# control_board_MCU.net
KiCad netlist of a schematic drawn in EAGLE
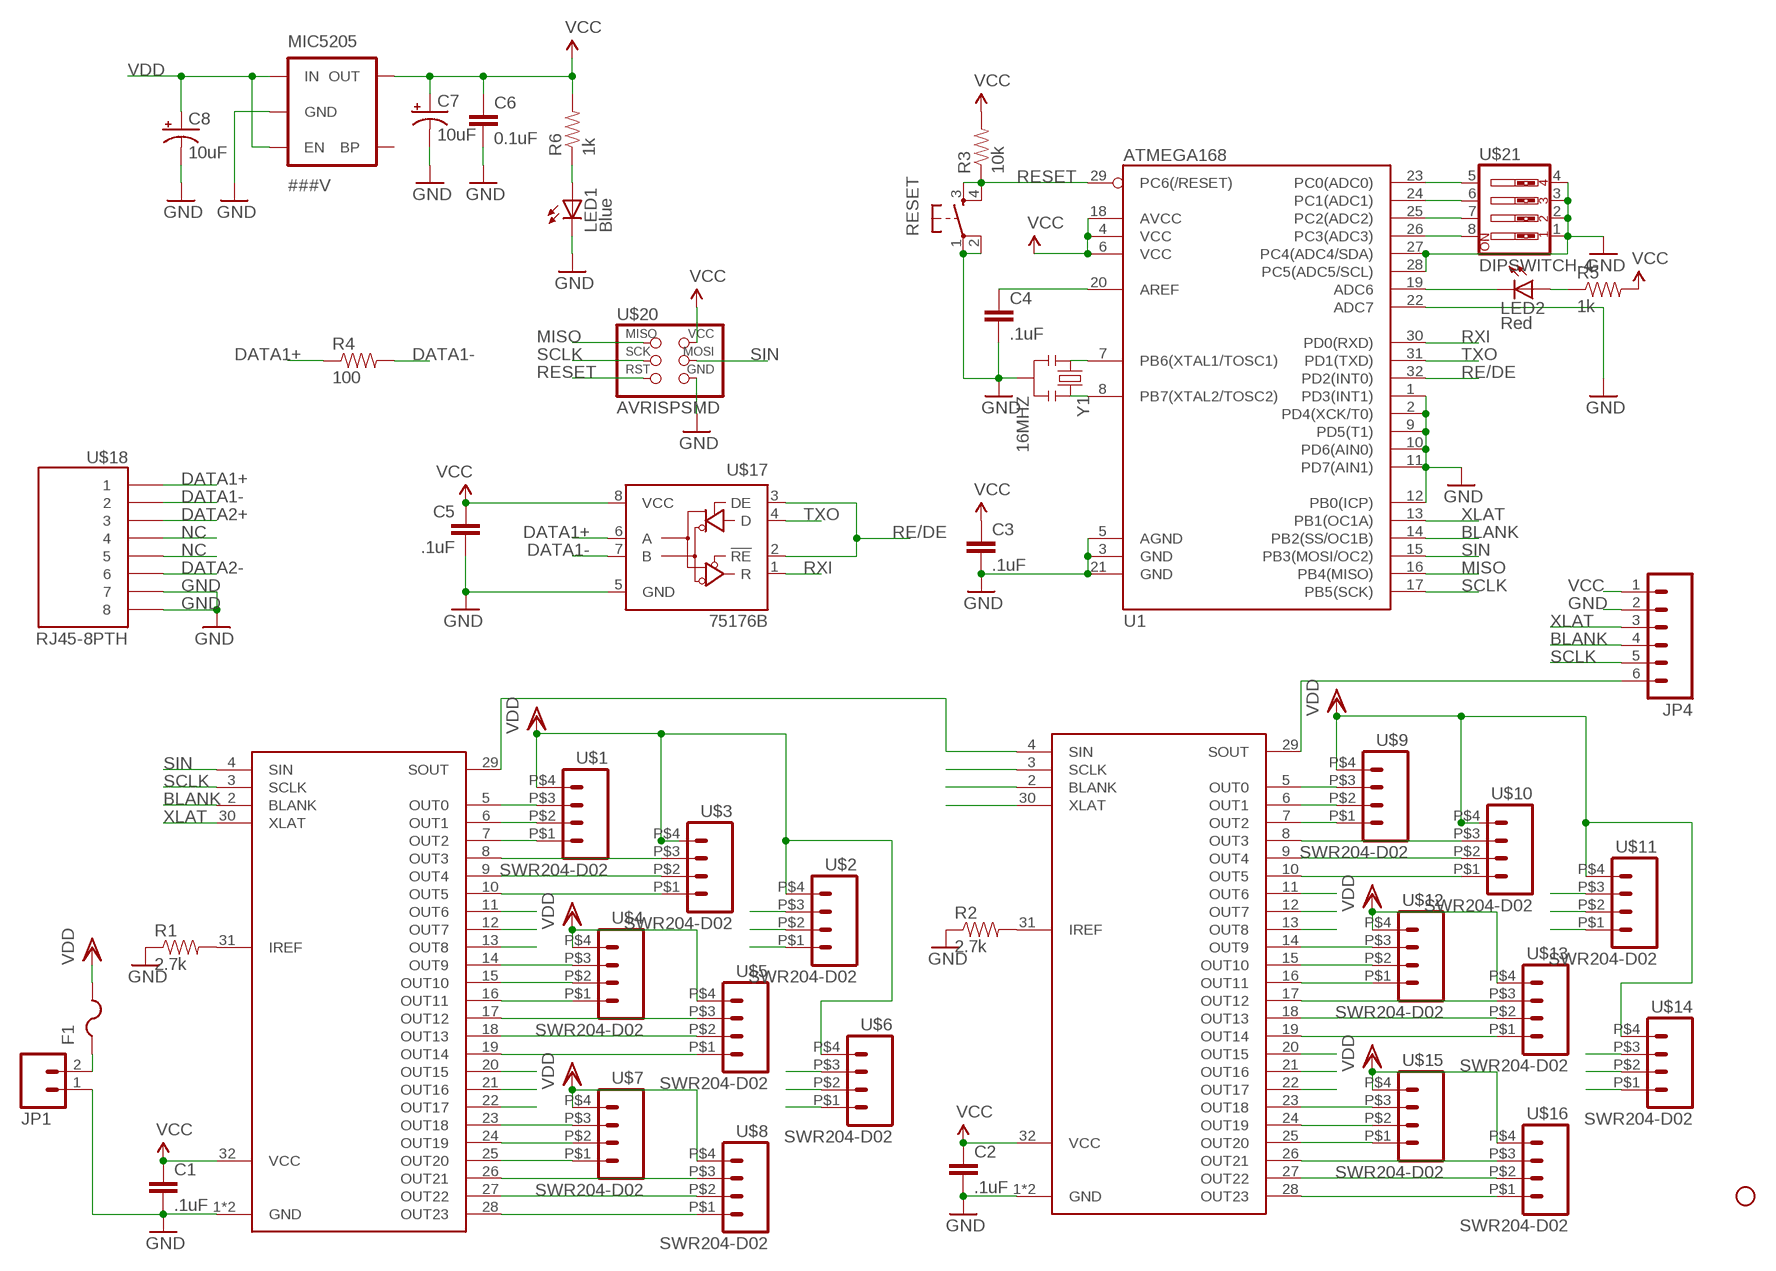
[diagram p0: schematic, sheet 1]

(export (version "E")
  (design (tool "Eeschema 10.0.6"))
  (components
    (comp (ref "C1")
      (value ".1uF")
      (footprint "eagle-import:0402-CAP")
      (libsource (lib "eagle-import") (part "CAP0402-CAP"))
    )
    (comp (ref "C2")
      (value ".1uF")
      (footprint "eagle-import:0402-CAP")
      (libsource (lib "eagle-import") (part "CAP0402-CAP"))
    )
    (comp (ref "C3")
      (value ".1uF")
      (footprint "eagle-import:0402-CAP")
      (libsource (lib "eagle-import") (part "CAP0402-CAP"))
    )
    (comp (ref "C4")
      (value ".1uF")
      (footprint "eagle-import:0402-CAP")
      (libsource (lib "eagle-import") (part "CAP0402-CAP"))
    )
    (comp (ref "C5")
      (value ".1uF")
      (footprint "eagle-import:0402-CAP")
      (libsource (lib "eagle-import") (part "CAP0402-CAP"))
    )
    (comp (ref "C6")
      (value "0.1uF")
      (footprint "eagle-import:0402-CAP")
      (libsource (lib "eagle-import") (part "CAP0402-CAP"))
    )
    (comp (ref "C7")
      (value "10uF")
      (footprint "eagle-import:EIA3216")
      (libsource (lib "eagle-import") (part "CAP_POL1206"))
    )
    (comp (ref "C8")
      (value "10uF")
      (footprint "eagle-import:EIA3216")
      (libsource (lib "eagle-import") (part "CAP_POL1206"))
    )
    (comp (ref "F1")
      (value "PTCFUSE-1812")
      (footprint "eagle-import:1812")
      (libsource (lib "eagle-import") (part "PTCFUSE-1812"))
    )
    (comp (ref "JP1")
      (value "M02-JST-2MM-SMT")
      (footprint "eagle-import:JST-2-SMD")
      (libsource (lib "eagle-import") (part "M02-JST-2MM-SMT"))
    )
    (comp (ref "JP4")
      (value "M06LOCK")
      (footprint "eagle-import:1X06_LOCK")
      (libsource (lib "eagle-import") (part "M06LOCK"))
    )
    (comp (ref "LED1")
      (value "Blue")
      (footprint "eagle-import:LED-0603")
      (libsource (lib "eagle-import") (part "LED0603"))
    )
    (comp (ref "LED2")
      (value "Red")
      (footprint "eagle-import:LED-0603")
      (libsource (lib "eagle-import") (part "LED0603"))
    )
    (comp (ref "MIC5205")
      (value "###V")
      (footprint "eagle-import:SOT23-5")
      (libsource (lib "eagle-import") (part "V_REG_LDOSMD"))
    )
    (comp (ref "R1")
      (value "2.7k")
      (footprint "eagle-import:0603-RES")
      (libsource (lib "eagle-import") (part "SparkFun-Resistors_RESISTOR0603-RES"))
    )
    (comp (ref "R2")
      (value "2.7k")
      (footprint "eagle-import:0603-RES")
      (libsource (lib "eagle-import") (part "SparkFun-Resistors_RESISTOR0603-RES"))
    )
    (comp (ref "R3")
      (value "10k")
      (footprint "eagle-import:0402-RES")
      (libsource (lib "eagle-import") (part "RESISTOR0402-RES"))
    )
    (comp (ref "R4")
      (value "100")
      (footprint "eagle-import:1206")
      (libsource (lib "eagle-import") (part "SparkFun-Passives_RESISTOR1206"))
    )
    (comp (ref "R5")
      (value "1k")
      (footprint "eagle-import:C0402")
      (libsource (lib "eagle-import") (part "RESISTOR0402"))
    )
    (comp (ref "R6")
      (value "1k")
      (footprint "eagle-import:C0402")
      (libsource (lib "eagle-import") (part "RESISTOR0402"))
    )
    (comp (ref "RESET")
      (value "TAC_SWITCHSMD")
      (footprint "eagle-import:TACTILE_SWITCH_SMD")
      (libsource (lib "eagle-import") (part "TAC_SWITCHSMD"))
    )
    (comp (ref "STANDOFF1")
      (value "STAND-OFF")
      (footprint "eagle-import:STAND-OFF")
      (libsource (lib "eagle-import") (part "STAND-OFF"))
    )
    (comp (ref "TLC5947")
      (value "TLC5947DAP")
      (footprint "eagle-import:DAP")
      (libsource (lib "eagle-import") (part "TLC5947DAP"))
    )
    (comp (ref "TLC5947-2")
      (value "TLC5947DAP")
      (footprint "eagle-import:DAP")
      (libsource (lib "eagle-import") (part "TLC5947DAP"))
    )
    (comp (ref "U$1")
      (value "SWR204-D02")
      (footprint "eagle-import:SWR204")
      (libsource (lib "eagle-import") (part "SWR204-D02"))
    )
    (comp (ref "U$2")
      (value "SWR204-D02")
      (footprint "eagle-import:SWR204")
      (libsource (lib "eagle-import") (part "SWR204-D02"))
    )
    (comp (ref "U$3")
      (value "SWR204-D02")
      (footprint "eagle-import:SWR204")
      (libsource (lib "eagle-import") (part "SWR204-D02"))
    )
    (comp (ref "U$4")
      (value "SWR204-D02")
      (footprint "eagle-import:SWR204")
      (libsource (lib "eagle-import") (part "SWR204-D02"))
    )
    (comp (ref "U$5")
      (value "SWR204-D02")
      (footprint "eagle-import:SWR204")
      (libsource (lib "eagle-import") (part "SWR204-D02"))
    )
    (comp (ref "U$6")
      (value "SWR204-D02")
      (footprint "eagle-import:SWR204")
      (libsource (lib "eagle-import") (part "SWR204-D02"))
    )
    (comp (ref "U$7")
      (value "SWR204-D02")
      (footprint "eagle-import:SWR204")
      (libsource (lib "eagle-import") (part "SWR204-D02"))
    )
    (comp (ref "U$8")
      (value "SWR204-D02")
      (footprint "eagle-import:SWR204")
      (libsource (lib "eagle-import") (part "SWR204-D02"))
    )
    (comp (ref "U$9")
      (value "SWR204-D02")
      (footprint "eagle-import:SWR204")
      (libsource (lib "eagle-import") (part "SWR204-D02"))
    )
    (comp (ref "U$10")
      (value "SWR204-D02")
      (footprint "eagle-import:SWR204")
      (libsource (lib "eagle-import") (part "SWR204-D02"))
    )
    (comp (ref "U$11")
      (value "SWR204-D02")
      (footprint "eagle-import:SWR204")
      (libsource (lib "eagle-import") (part "SWR204-D02"))
    )
    (comp (ref "U$12")
      (value "SWR204-D02")
      (footprint "eagle-import:SWR204")
      (libsource (lib "eagle-import") (part "SWR204-D02"))
    )
    (comp (ref "U$13")
      (value "SWR204-D02")
      (footprint "eagle-import:SWR204")
      (libsource (lib "eagle-import") (part "SWR204-D02"))
    )
    (comp (ref "U$14")
      (value "SWR204-D02")
      (footprint "eagle-import:SWR204")
      (libsource (lib "eagle-import") (part "SWR204-D02"))
    )
    (comp (ref "U$15")
      (value "SWR204-D02")
      (footprint "eagle-import:SWR204")
      (libsource (lib "eagle-import") (part "SWR204-D02"))
    )
    (comp (ref "U$16")
      (value "SWR204-D02")
      (footprint "eagle-import:SWR204")
      (libsource (lib "eagle-import") (part "SWR204-D02"))
    )
    (comp (ref "U$17")
      (value "75176B")
      (footprint "eagle-import:D_R-PDSO-G8")
      (libsource (lib "eagle-import") (part "75176B"))
    )
    (comp (ref "U$18")
      (value "RJ45-8PTH")
      (footprint "eagle-import:RJ45-8")
      (libsource (lib "eagle-import") (part "RJ45-8PTH"))
    )
    (comp (ref "U$20")
      (value "AVRISPSMD")
      (footprint "eagle-import:2X03SMD")
      (libsource (lib "eagle-import") (part "AVRISPSMD"))
    )
    (comp (ref "U$21")
      (value "DIPSWITCH-4")
      (footprint "eagle-import:DIPSWITCH-04")
      (libsource (lib "eagle-import") (part "DIPSWITCH-4"))
    )
    (comp (ref "U1")
      (value "ATMEGA168")
      (footprint "eagle-import:TQFP32-08")
      (libsource (lib "eagle-import") (part "ATMEGA168"))
    )
    (comp (ref "Y1")
      (value "16MHZ")
      (footprint "eagle-import:RESONATOR-SMD")
      (libsource (lib "eagle-import") (part "RESONATOR8MHZ"))
    )
  )
  (nets
    (net (code "1") (name "/BLANK") (class "Default")
      (node (ref "JP4") (pin "4") (pinfunction "4_4") (pintype "passive"))
      (node (ref "TLC5947") (pin "2") (pinfunction "BLANK_2") (pintype "bidirectional"))
      (node (ref "TLC5947-2") (pin "2") (pinfunction "BLANK_2") (pintype "bidirectional"))
      (node (ref "U1") (pin "14") (pinfunction "PB2(SS/OC1B)_14") (pintype "bidirectional"))
    )
    (net (code "2") (name "/DATA1+") (class "Default")
      (node (ref "R4") (pin "1") (pinfunction "1_1") (pintype "passive"))
      (node (ref "U$17") (pin "6") (pinfunction "A_6") (pintype "output"))
      (node (ref "U$18") (pin "1") (pinfunction "1_1") (pintype "bidirectional"))
    )
    (net (code "3") (name "/DATA1-") (class "Default")
      (node (ref "R4") (pin "2") (pinfunction "2_2") (pintype "passive"))
      (node (ref "U$17") (pin "7") (pinfunction "B_7") (pintype "output"))
      (node (ref "U$18") (pin "2") (pinfunction "2_2") (pintype "bidirectional"))
    )
    (net (code "4") (name "/DATA2+") (class "Default")
      (node (ref "U$18") (pin "3") (pinfunction "3_3") (pintype "bidirectional"))
    )
    (net (code "5") (name "/DATA2-") (class "Default")
      (node (ref "U$18") (pin "6") (pinfunction "6_6") (pintype "bidirectional"))
    )
    (net (code "6") (name "/MISO") (class "Default")
      (node (ref "U$20") (pin "1") (pinfunction "MISO_1") (pintype "passive"))
      (node (ref "U1") (pin "16") (pinfunction "PB4(MISO)_16") (pintype "bidirectional"))
    )
    (net (code "7") (name "/NC") (class "Default")
      (node (ref "U$18") (pin "4") (pinfunction "4_4") (pintype "bidirectional"))
      (node (ref "U$18") (pin "5") (pinfunction "5_5") (pintype "bidirectional"))
    )
    (net (code "8") (name "/OUT6") (class "Default")
      (node (ref "TLC5947") (pin "11") (pinfunction "OUT6_11") (pintype "bidirectional"))
      (node (ref "U$2") (pin "P$3") (pinfunction "3_P$3") (pintype "passive"))
    )
    (net (code "9") (name "/OUT7") (class "Default")
      (node (ref "TLC5947") (pin "12") (pinfunction "OUT7_12") (pintype "bidirectional"))
      (node (ref "U$2") (pin "P$2") (pinfunction "2_P$2") (pintype "passive"))
    )
    (net (code "10") (name "/OUT8") (class "Default")
      (node (ref "TLC5947") (pin "13") (pinfunction "OUT8_13") (pintype "bidirectional"))
      (node (ref "U$2") (pin "P$1") (pinfunction "1_P$1") (pintype "passive"))
    )
    (net (code "11") (name "/OUT15") (class "Default")
      (node (ref "TLC5947") (pin "20") (pinfunction "OUT15_20") (pintype "bidirectional"))
      (node (ref "U$6") (pin "P$3") (pinfunction "3_P$3") (pintype "passive"))
    )
    (net (code "12") (name "/OUT16") (class "Default")
      (node (ref "TLC5947") (pin "21") (pinfunction "OUT16_21") (pintype "bidirectional"))
      (node (ref "U$6") (pin "P$2") (pinfunction "2_P$2") (pintype "passive"))
    )
    (net (code "13") (name "/OUT17") (class "Default")
      (node (ref "TLC5947") (pin "22") (pinfunction "OUT17_22") (pintype "bidirectional"))
      (node (ref "U$6") (pin "P$1") (pinfunction "1_P$1") (pintype "passive"))
    )
    (net (code "14") (name "/OUT30") (class "Default")
      (node (ref "TLC5947-2") (pin "11") (pinfunction "OUT6_11") (pintype "bidirectional"))
      (node (ref "U$11") (pin "P$3") (pinfunction "3_P$3") (pintype "passive"))
    )
    (net (code "15") (name "/OUT31") (class "Default")
      (node (ref "TLC5947-2") (pin "12") (pinfunction "OUT7_12") (pintype "bidirectional"))
      (node (ref "U$11") (pin "P$2") (pinfunction "2_P$2") (pintype "passive"))
    )
    (net (code "16") (name "/OUT32") (class "Default")
      (node (ref "TLC5947-2") (pin "13") (pinfunction "OUT8_13") (pintype "bidirectional"))
      (node (ref "U$11") (pin "P$1") (pinfunction "1_P$1") (pintype "passive"))
    )
    (net (code "17") (name "/OUT39") (class "Default")
      (node (ref "TLC5947-2") (pin "20") (pinfunction "OUT15_20") (pintype "bidirectional"))
      (node (ref "U$14") (pin "P$3") (pinfunction "3_P$3") (pintype "passive"))
    )
    (net (code "18") (name "/OUT40") (class "Default")
      (node (ref "TLC5947-2") (pin "21") (pinfunction "OUT16_21") (pintype "bidirectional"))
      (node (ref "U$14") (pin "P$2") (pinfunction "2_P$2") (pintype "passive"))
    )
    (net (code "19") (name "/OUT41") (class "Default")
      (node (ref "TLC5947-2") (pin "22") (pinfunction "OUT17_22") (pintype "bidirectional"))
      (node (ref "U$14") (pin "P$1") (pinfunction "1_P$1") (pintype "passive"))
    )
    (net (code "20") (name "/RESET") (class "Default")
      (node (ref "R3") (pin "1") (pinfunction "1_1") (pintype "passive"))
      (node (ref "RESET") (pin "3") (pinfunction "3_3") (pintype "passive"))
      (node (ref "RESET") (pin "4") (pinfunction "4_4") (pintype "passive"))
      (node (ref "U$20") (pin "5") (pinfunction "RST_5") (pintype "passive"))
      (node (ref "U1") (pin "29") (pinfunction "PC6(/RESET)_29") (pintype "bidirectional"))
    )
    (net (code "21") (name "/RE{slash}DE") (class "Default")
      (node (ref "U$17") (pin "2") (pinfunction "~{RE}_2") (pintype "input"))
      (node (ref "U$17") (pin "3") (pinfunction "DE_3") (pintype "input"))
      (node (ref "U1") (pin "32") (pinfunction "PD2(INT0)_32") (pintype "bidirectional"))
    )
    (net (code "22") (name "/RXI") (class "Default")
      (node (ref "U$17") (pin "1") (pinfunction "R_1") (pintype "input"))
      (node (ref "U1") (pin "30") (pinfunction "PD0(RXD)_30") (pintype "bidirectional"))
    )
    (net (code "23") (name "/SCLK") (class "Default")
      (node (ref "JP4") (pin "5") (pinfunction "5_5") (pintype "passive"))
      (node (ref "TLC5947") (pin "3") (pinfunction "SCLK_3") (pintype "bidirectional"))
      (node (ref "TLC5947-2") (pin "3") (pinfunction "SCLK_3") (pintype "bidirectional"))
      (node (ref "U$20") (pin "3") (pinfunction "SCK_3") (pintype "passive"))
      (node (ref "U1") (pin "17") (pinfunction "PB5(SCK)_17") (pintype "bidirectional"))
    )
    (net (code "24") (name "/SIN") (class "Default")
      (node (ref "TLC5947") (pin "4") (pinfunction "SIN_4") (pintype "bidirectional"))
      (node (ref "U$20") (pin "4") (pinfunction "MOSI_4") (pintype "passive"))
      (node (ref "U1") (pin "15") (pinfunction "PB3(MOSI/OC2)_15") (pintype "bidirectional"))
    )
    (net (code "25") (name "/TXO") (class "Default")
      (node (ref "U$17") (pin "4") (pinfunction "D_4") (pintype "input"))
      (node (ref "U1") (pin "31") (pinfunction "PD1(TXD)_31") (pintype "bidirectional"))
    )
    (net (code "26") (name "/XLAT") (class "Default")
      (node (ref "JP4") (pin "3") (pinfunction "3_3") (pintype "passive"))
      (node (ref "TLC5947") (pin "30") (pinfunction "XLAT_30") (pintype "bidirectional"))
      (node (ref "TLC5947-2") (pin "30") (pinfunction "XLAT_30") (pintype "bidirectional"))
      (node (ref "U1") (pin "13") (pinfunction "PB1(OC1A)_13") (pintype "bidirectional"))
    )
    (net (code "27") (name "GND") (class "Default")
      (node (ref "C1") (pin "2") (pinfunction "2_2") (pintype "passive"))
      (node (ref "C2") (pin "2") (pinfunction "2_2") (pintype "passive"))
      (node (ref "C3") (pin "2") (pinfunction "2_2") (pintype "passive"))
      (node (ref "C4") (pin "2") (pinfunction "2_2") (pintype "passive"))
      (node (ref "C5") (pin "2") (pinfunction "2_2") (pintype "passive"))
      (node (ref "C6") (pin "2") (pinfunction "2_2") (pintype "passive"))
      (node (ref "C7") (pin "C") (pinfunction "-_C") (pintype "passive"))
      (node (ref "C8") (pin "C") (pinfunction "-_C") (pintype "passive"))
      (node (ref "JP1") (pin "1") (pinfunction "2_1") (pintype "passive"))
      (node (ref "JP4") (pin "2") (pinfunction "2_2") (pintype "passive"))
      (node (ref "LED1") (pin "C") (pinfunction "C_C") (pintype "passive"))
      (node (ref "MIC5205") (pin "2") (pinfunction "GND_2") (pintype "input"))
      (node (ref "R1") (pin "1") (pinfunction "1_1") (pintype "passive"))
      (node (ref "R2") (pin "1") (pinfunction "1_1") (pintype "passive"))
      (node (ref "RESET") (pin "1") (pinfunction "1_1") (pintype "passive"))
      (node (ref "RESET") (pin "2") (pinfunction "2_2") (pintype "passive"))
      (node (ref "TLC5947") (pin "1") (pinfunction "GND_1") (pintype "bidirectional"))
      (node (ref "TLC5947") (pin "GND") (pinfunction "GND_GND") (pintype "bidirectional"))
      (node (ref "TLC5947-2") (pin "1") (pinfunction "GND_1") (pintype "bidirectional"))
      (node (ref "TLC5947-2") (pin "GND") (pinfunction "GND_GND") (pintype "bidirectional"))
      (node (ref "U$17") (pin "5") (pinfunction "GND_5") (pintype "power_in"))
      (node (ref "U$18") (pin "7") (pinfunction "7_7") (pintype "bidirectional"))
      (node (ref "U$18") (pin "8") (pinfunction "8_8") (pintype "bidirectional"))
      (node (ref "U$20") (pin "6") (pinfunction "GND_6") (pintype "passive"))
      (node (ref "U$21") (pin "1") (pinfunction "1_1") (pintype "passive"))
      (node (ref "U$21") (pin "2") (pinfunction "2_2") (pintype "passive"))
      (node (ref "U$21") (pin "3") (pinfunction "3_3") (pintype "passive"))
      (node (ref "U$21") (pin "4") (pinfunction "4_4") (pintype "passive"))
      (node (ref "U1") (pin "1") (pinfunction "PD3(INT1)_1") (pintype "bidirectional"))
      (node (ref "U1") (pin "10") (pinfunction "PD6(AIN0)_10") (pintype "bidirectional"))
      (node (ref "U1") (pin "11") (pinfunction "PD7(AIN1)_11") (pintype "bidirectional"))
      (node (ref "U1") (pin "12") (pinfunction "PB0(ICP)_12") (pintype "bidirectional"))
      (node (ref "U1") (pin "2") (pinfunction "PD4(XCK/T0)_2") (pintype "bidirectional"))
      (node (ref "U1") (pin "21") (pinfunction "GND_21") (pintype "bidirectional"))
      (node (ref "U1") (pin "22") (pinfunction "ADC7_22") (pintype "bidirectional"))
      (node (ref "U1") (pin "27") (pinfunction "PC4(ADC4/SDA)_27") (pintype "bidirectional"))
      (node (ref "U1") (pin "28") (pinfunction "PC5(ADC5/SCL)_28") (pintype "bidirectional"))
      (node (ref "U1") (pin "3") (pinfunction "GND_3") (pintype "bidirectional"))
      (node (ref "U1") (pin "5") (pinfunction "AGND_5") (pintype "bidirectional"))
      (node (ref "U1") (pin "9") (pinfunction "PD5(T1)_9") (pintype "bidirectional"))
      (node (ref "Y1") (pin "2") (pinfunction "2_2") (pintype "passive"))
    )
    (net (code "28") (name "Net-(JP1-1)") (class "Default")
      (node (ref "F1") (pin "1") (pinfunction "1_1") (pintype "passive"))
      (node (ref "JP1") (pin "2") (pinfunction "1_2") (pintype "passive"))
    )
    (net (code "29") (name "Net-(LED1-PadA)") (class "Default")
      (node (ref "LED1") (pin "A") (pinfunction "A_A") (pintype "passive"))
      (node (ref "R6") (pin "1") (pinfunction "1_1") (pintype "passive"))
    )
    (net (code "30") (name "Net-(LED2-PadA)") (class "Default")
      (node (ref "LED2") (pin "A") (pinfunction "A_A") (pintype "passive"))
      (node (ref "R5") (pin "1") (pinfunction "1_1") (pintype "passive"))
    )
    (net (code "31") (name "Net-(TLC5947-2-IREF)") (class "Default")
      (node (ref "R2") (pin "2") (pinfunction "2_2") (pintype "passive"))
      (node (ref "TLC5947-2") (pin "31") (pinfunction "IREF_31") (pintype "bidirectional"))
    )
    (net (code "32") (name "Net-(TLC5947-2-OUT0)") (class "Default")
      (node (ref "TLC5947-2") (pin "5") (pinfunction "OUT0_5") (pintype "bidirectional"))
      (node (ref "U$9") (pin "P$3") (pinfunction "3_P$3") (pintype "passive"))
    )
    (net (code "33") (name "Net-(TLC5947-2-OUT1)") (class "Default")
      (node (ref "TLC5947-2") (pin "6") (pinfunction "OUT1_6") (pintype "bidirectional"))
      (node (ref "U$9") (pin "P$2") (pinfunction "2_P$2") (pintype "passive"))
    )
    (net (code "34") (name "Net-(TLC5947-2-OUT2)") (class "Default")
      (node (ref "TLC5947-2") (pin "7") (pinfunction "OUT2_7") (pintype "bidirectional"))
      (node (ref "U$9") (pin "P$1") (pinfunction "1_P$1") (pintype "passive"))
    )
    (net (code "35") (name "Net-(TLC5947-2-OUT3)") (class "Default")
      (node (ref "TLC5947-2") (pin "8") (pinfunction "OUT3_8") (pintype "bidirectional"))
      (node (ref "U$10") (pin "P$3") (pinfunction "3_P$3") (pintype "passive"))
    )
    (net (code "36") (name "Net-(TLC5947-2-OUT4)") (class "Default")
      (node (ref "TLC5947-2") (pin "9") (pinfunction "OUT4_9") (pintype "bidirectional"))
      (node (ref "U$10") (pin "P$2") (pinfunction "2_P$2") (pintype "passive"))
    )
    (net (code "37") (name "Net-(TLC5947-2-OUT5)") (class "Default")
      (node (ref "TLC5947-2") (pin "10") (pinfunction "OUT5_10") (pintype "bidirectional"))
      (node (ref "U$10") (pin "P$1") (pinfunction "1_P$1") (pintype "passive"))
    )
    (net (code "38") (name "Net-(TLC5947-2-OUT9)") (class "Default")
      (node (ref "TLC5947-2") (pin "14") (pinfunction "OUT9_14") (pintype "bidirectional"))
      (node (ref "U$12") (pin "P$3") (pinfunction "3_P$3") (pintype "passive"))
    )
    (net (code "39") (name "Net-(TLC5947-2-OUT10)") (class "Default")
      (node (ref "TLC5947-2") (pin "15") (pinfunction "OUT10_15") (pintype "bidirectional"))
      (node (ref "U$12") (pin "P$2") (pinfunction "2_P$2") (pintype "passive"))
    )
    (net (code "40") (name "Net-(TLC5947-2-OUT11)") (class "Default")
      (node (ref "TLC5947-2") (pin "16") (pinfunction "OUT11_16") (pintype "bidirectional"))
      (node (ref "U$12") (pin "P$1") (pinfunction "1_P$1") (pintype "passive"))
    )
    (net (code "41") (name "Net-(TLC5947-2-OUT12)") (class "Default")
      (node (ref "TLC5947-2") (pin "17") (pinfunction "OUT12_17") (pintype "bidirectional"))
      (node (ref "U$13") (pin "P$3") (pinfunction "3_P$3") (pintype "passive"))
    )
    (net (code "42") (name "Net-(TLC5947-2-OUT13)") (class "Default")
      (node (ref "TLC5947-2") (pin "18") (pinfunction "OUT13_18") (pintype "bidirectional"))
      (node (ref "U$13") (pin "P$2") (pinfunction "2_P$2") (pintype "passive"))
    )
    (net (code "43") (name "Net-(TLC5947-2-OUT14)") (class "Default")
      (node (ref "TLC5947-2") (pin "19") (pinfunction "OUT14_19") (pintype "bidirectional"))
      (node (ref "U$13") (pin "P$1") (pinfunction "1_P$1") (pintype "passive"))
    )
    (net (code "44") (name "Net-(TLC5947-2-OUT18)") (class "Default")
      (node (ref "TLC5947-2") (pin "23") (pinfunction "OUT18_23") (pintype "bidirectional"))
      (node (ref "U$15") (pin "P$3") (pinfunction "3_P$3") (pintype "passive"))
    )
    (net (code "45") (name "Net-(TLC5947-2-OUT19)") (class "Default")
      (node (ref "TLC5947-2") (pin "24") (pinfunction "OUT19_24") (pintype "bidirectional"))
      (node (ref "U$15") (pin "P$2") (pinfunction "2_P$2") (pintype "passive"))
    )
    (net (code "46") (name "Net-(TLC5947-2-OUT20)") (class "Default")
      (node (ref "TLC5947-2") (pin "25") (pinfunction "OUT20_25") (pintype "bidirectional"))
      (node (ref "U$15") (pin "P$1") (pinfunction "1_P$1") (pintype "passive"))
    )
    (net (code "47") (name "Net-(TLC5947-2-OUT21)") (class "Default")
      (node (ref "TLC5947-2") (pin "26") (pinfunction "OUT21_26") (pintype "bidirectional"))
      (node (ref "U$16") (pin "P$3") (pinfunction "3_P$3") (pintype "passive"))
    )
    (net (code "48") (name "Net-(TLC5947-2-OUT22)") (class "Default")
      (node (ref "TLC5947-2") (pin "27") (pinfunction "OUT22_27") (pintype "bidirectional"))
      (node (ref "U$16") (pin "P$2") (pinfunction "2_P$2") (pintype "passive"))
    )
    (net (code "49") (name "Net-(TLC5947-2-OUT23)") (class "Default")
      (node (ref "TLC5947-2") (pin "28") (pinfunction "OUT23_28") (pintype "bidirectional"))
      (node (ref "U$16") (pin "P$1") (pinfunction "1_P$1") (pintype "passive"))
    )
    (net (code "50") (name "Net-(TLC5947-2-SIN)") (class "Default")
      (node (ref "TLC5947") (pin "29") (pinfunction "SOUT_29") (pintype "bidirectional"))
      (node (ref "TLC5947-2") (pin "4") (pinfunction "SIN_4") (pintype "bidirectional"))
    )
    (net (code "51") (name "Net-(TLC5947-2-SOUT)") (class "Default")
      (node (ref "JP4") (pin "6") (pinfunction "6_6") (pintype "passive"))
      (node (ref "TLC5947-2") (pin "29") (pinfunction "SOUT_29") (pintype "bidirectional"))
    )
    (net (code "52") (name "Net-(TLC5947-IREF)") (class "Default")
      (node (ref "R1") (pin "2") (pinfunction "2_2") (pintype "passive"))
      (node (ref "TLC5947") (pin "31") (pinfunction "IREF_31") (pintype "bidirectional"))
    )
    (net (code "53") (name "Net-(TLC5947-OUT0)") (class "Default")
      (node (ref "TLC5947") (pin "5") (pinfunction "OUT0_5") (pintype "bidirectional"))
      (node (ref "U$1") (pin "P$3") (pinfunction "3_P$3") (pintype "passive"))
    )
    (net (code "54") (name "Net-(TLC5947-OUT1)") (class "Default")
      (node (ref "TLC5947") (pin "6") (pinfunction "OUT1_6") (pintype "bidirectional"))
      (node (ref "U$1") (pin "P$2") (pinfunction "2_P$2") (pintype "passive"))
    )
    (net (code "55") (name "Net-(TLC5947-OUT2)") (class "Default")
      (node (ref "TLC5947") (pin "7") (pinfunction "OUT2_7") (pintype "bidirectional"))
      (node (ref "U$1") (pin "P$1") (pinfunction "1_P$1") (pintype "passive"))
    )
    (net (code "56") (name "Net-(TLC5947-OUT3)") (class "Default")
      (node (ref "TLC5947") (pin "8") (pinfunction "OUT3_8") (pintype "bidirectional"))
      (node (ref "U$3") (pin "P$3") (pinfunction "3_P$3") (pintype "passive"))
    )
    (net (code "57") (name "Net-(TLC5947-OUT4)") (class "Default")
      (node (ref "TLC5947") (pin "9") (pinfunction "OUT4_9") (pintype "bidirectional"))
      (node (ref "U$3") (pin "P$2") (pinfunction "2_P$2") (pintype "passive"))
    )
    (net (code "58") (name "Net-(TLC5947-OUT5)") (class "Default")
      (node (ref "TLC5947") (pin "10") (pinfunction "OUT5_10") (pintype "bidirectional"))
      (node (ref "U$3") (pin "P$1") (pinfunction "1_P$1") (pintype "passive"))
    )
    (net (code "59") (name "Net-(TLC5947-OUT9)") (class "Default")
      (node (ref "TLC5947") (pin "14") (pinfunction "OUT9_14") (pintype "bidirectional"))
      (node (ref "U$4") (pin "P$3") (pinfunction "3_P$3") (pintype "passive"))
    )
    (net (code "60") (name "Net-(TLC5947-OUT10)") (class "Default")
      (node (ref "TLC5947") (pin "15") (pinfunction "OUT10_15") (pintype "bidirectional"))
      (node (ref "U$4") (pin "P$2") (pinfunction "2_P$2") (pintype "passive"))
    )
    (net (code "61") (name "Net-(TLC5947-OUT11)") (class "Default")
      (node (ref "TLC5947") (pin "16") (pinfunction "OUT11_16") (pintype "bidirectional"))
      (node (ref "U$4") (pin "P$1") (pinfunction "1_P$1") (pintype "passive"))
    )
    (net (code "62") (name "Net-(TLC5947-OUT12)") (class "Default")
      (node (ref "TLC5947") (pin "17") (pinfunction "OUT12_17") (pintype "bidirectional"))
      (node (ref "U$5") (pin "P$3") (pinfunction "3_P$3") (pintype "passive"))
    )
    (net (code "63") (name "Net-(TLC5947-OUT13)") (class "Default")
      (node (ref "TLC5947") (pin "18") (pinfunction "OUT13_18") (pintype "bidirectional"))
      (node (ref "U$5") (pin "P$2") (pinfunction "2_P$2") (pintype "passive"))
    )
    (net (code "64") (name "Net-(TLC5947-OUT14)") (class "Default")
      (node (ref "TLC5947") (pin "19") (pinfunction "OUT14_19") (pintype "bidirectional"))
      (node (ref "U$5") (pin "P$1") (pinfunction "1_P$1") (pintype "passive"))
    )
    (net (code "65") (name "Net-(TLC5947-OUT18)") (class "Default")
      (node (ref "TLC5947") (pin "23") (pinfunction "OUT18_23") (pintype "bidirectional"))
      (node (ref "U$7") (pin "P$3") (pinfunction "3_P$3") (pintype "passive"))
    )
    (net (code "66") (name "Net-(TLC5947-OUT19)") (class "Default")
      (node (ref "TLC5947") (pin "24") (pinfunction "OUT19_24") (pintype "bidirectional"))
      (node (ref "U$7") (pin "P$2") (pinfunction "2_P$2") (pintype "passive"))
    )
    (net (code "67") (name "Net-(TLC5947-OUT20)") (class "Default")
      (node (ref "TLC5947") (pin "25") (pinfunction "OUT20_25") (pintype "bidirectional"))
      (node (ref "U$7") (pin "P$1") (pinfunction "1_P$1") (pintype "passive"))
    )
    (net (code "68") (name "Net-(TLC5947-OUT21)") (class "Default")
      (node (ref "TLC5947") (pin "26") (pinfunction "OUT21_26") (pintype "bidirectional"))
      (node (ref "U$8") (pin "P$3") (pinfunction "3_P$3") (pintype "passive"))
    )
    (net (code "69") (name "Net-(TLC5947-OUT22)") (class "Default")
      (node (ref "TLC5947") (pin "27") (pinfunction "OUT22_27") (pintype "bidirectional"))
      (node (ref "U$8") (pin "P$2") (pinfunction "2_P$2") (pintype "passive"))
    )
    (net (code "70") (name "Net-(TLC5947-OUT23)") (class "Default")
      (node (ref "TLC5947") (pin "28") (pinfunction "OUT23_28") (pintype "bidirectional"))
      (node (ref "U$8") (pin "P$1") (pinfunction "1_P$1") (pintype "passive"))
    )
    (net (code "71") (name "Net-(U1-ADC6)") (class "Default")
      (node (ref "LED2") (pin "C") (pinfunction "C_C") (pintype "passive"))
      (node (ref "U1") (pin "19") (pinfunction "ADC6_19") (pintype "bidirectional"))
    )
    (net (code "72") (name "Net-(U1-AREF)") (class "Default")
      (node (ref "C4") (pin "1") (pinfunction "1_1") (pintype "passive"))
      (node (ref "U1") (pin "20") (pinfunction "AREF_20") (pintype "bidirectional"))
    )
    (net (code "73") (name "Net-(U1-PB6(XTAL1{slash}TOSC1))") (class "Default")
      (node (ref "U1") (pin "7") (pinfunction "PB6(XTAL1/TOSC1)_7") (pintype "bidirectional"))
      (node (ref "Y1") (pin "1") (pinfunction "1_1") (pintype "passive"))
    )
    (net (code "74") (name "Net-(U1-PB7(XTAL2{slash}TOSC2))") (class "Default")
      (node (ref "U1") (pin "8") (pinfunction "PB7(XTAL2/TOSC2)_8") (pintype "bidirectional"))
      (node (ref "Y1") (pin "3") (pinfunction "3_3") (pintype "passive"))
    )
    (net (code "75") (name "Net-(U1-PC0(ADC0))") (class "Default")
      (node (ref "U$21") (pin "5") (pinfunction "5_5") (pintype "passive"))
      (node (ref "U1") (pin "23") (pinfunction "PC0(ADC0)_23") (pintype "bidirectional"))
    )
    (net (code "76") (name "Net-(U1-PC1(ADC1))") (class "Default")
      (node (ref "U$21") (pin "6") (pinfunction "6_6") (pintype "passive"))
      (node (ref "U1") (pin "24") (pinfunction "PC1(ADC1)_24") (pintype "bidirectional"))
    )
    (net (code "77") (name "Net-(U1-PC2(ADC2))") (class "Default")
      (node (ref "U$21") (pin "7") (pinfunction "7_7") (pintype "passive"))
      (node (ref "U1") (pin "25") (pinfunction "PC2(ADC2)_25") (pintype "bidirectional"))
    )
    (net (code "78") (name "Net-(U1-PC3(ADC3))") (class "Default")
      (node (ref "U$21") (pin "8") (pinfunction "8_8") (pintype "passive"))
      (node (ref "U1") (pin "26") (pinfunction "PC3(ADC3)_26") (pintype "bidirectional"))
    )
    (net (code "79") (name "VCC") (class "Default")
      (node (ref "C1") (pin "1") (pinfunction "1_1") (pintype "passive"))
      (node (ref "C2") (pin "1") (pinfunction "1_1") (pintype "passive"))
      (node (ref "C3") (pin "1") (pinfunction "1_1") (pintype "passive"))
      (node (ref "C5") (pin "1") (pinfunction "1_1") (pintype "passive"))
      (node (ref "C6") (pin "1") (pinfunction "1_1") (pintype "passive"))
      (node (ref "C7") (pin "A") (pinfunction "+_A") (pintype "passive"))
      (node (ref "JP4") (pin "1") (pinfunction "1_1") (pintype "passive"))
      (node (ref "MIC5205") (pin "5") (pinfunction "OUT_5") (pintype "passive"))
      (node (ref "R3") (pin "2") (pinfunction "2_2") (pintype "passive"))
      (node (ref "R5") (pin "2") (pinfunction "2_2") (pintype "passive"))
      (node (ref "R6") (pin "2") (pinfunction "2_2") (pintype "passive"))
      (node (ref "TLC5947") (pin "32") (pinfunction "VCC_32") (pintype "bidirectional"))
      (node (ref "TLC5947-2") (pin "32") (pinfunction "VCC_32") (pintype "bidirectional"))
      (node (ref "U$17") (pin "8") (pinfunction "VCC_8") (pintype "power_in"))
      (node (ref "U$20") (pin "2") (pinfunction "VCC_2") (pintype "passive"))
      (node (ref "U1") (pin "18") (pinfunction "AVCC_18") (pintype "bidirectional"))
      (node (ref "U1") (pin "4") (pinfunction "VCC_4") (pintype "bidirectional"))
      (node (ref "U1") (pin "6") (pinfunction "VCC_6") (pintype "bidirectional"))
    )
    (net (code "80") (name "VDD") (class "Default")
      (node (ref "C8") (pin "A") (pinfunction "+_A") (pintype "passive"))
      (node (ref "F1") (pin "2") (pinfunction "2_2") (pintype "passive"))
      (node (ref "MIC5205") (pin "1") (pinfunction "IN_1") (pintype "input"))
      (node (ref "MIC5205") (pin "3") (pinfunction "EN_3") (pintype "input"))
      (node (ref "U$1") (pin "P$4") (pinfunction "4_P$4") (pintype "passive"))
      (node (ref "U$10") (pin "P$4") (pinfunction "4_P$4") (pintype "passive"))
      (node (ref "U$11") (pin "P$4") (pinfunction "4_P$4") (pintype "passive"))
      (node (ref "U$12") (pin "P$4") (pinfunction "4_P$4") (pintype "passive"))
      (node (ref "U$13") (pin "P$4") (pinfunction "4_P$4") (pintype "passive"))
      (node (ref "U$14") (pin "P$4") (pinfunction "4_P$4") (pintype "passive"))
      (node (ref "U$15") (pin "P$4") (pinfunction "4_P$4") (pintype "passive"))
      (node (ref "U$16") (pin "P$4") (pinfunction "4_P$4") (pintype "passive"))
      (node (ref "U$2") (pin "P$4") (pinfunction "4_P$4") (pintype "passive"))
      (node (ref "U$3") (pin "P$4") (pinfunction "4_P$4") (pintype "passive"))
      (node (ref "U$4") (pin "P$4") (pinfunction "4_P$4") (pintype "passive"))
      (node (ref "U$5") (pin "P$4") (pinfunction "4_P$4") (pintype "passive"))
      (node (ref "U$6") (pin "P$4") (pinfunction "4_P$4") (pintype "passive"))
      (node (ref "U$7") (pin "P$4") (pinfunction "4_P$4") (pintype "passive"))
      (node (ref "U$8") (pin "P$4") (pinfunction "4_P$4") (pintype "passive"))
      (node (ref "U$9") (pin "P$4") (pinfunction "4_P$4") (pintype "passive"))
    )
    (net (code "81") (name "unconnected-(MIC5205-BP-Pad4)") (class "Default")
      (node (ref "MIC5205") (pin "4") (pinfunction "BP_4") (pintype "input"))
    )
  )
)
